# 04_io.net
KiCad netlist of a schematic drawn in Altium Designer
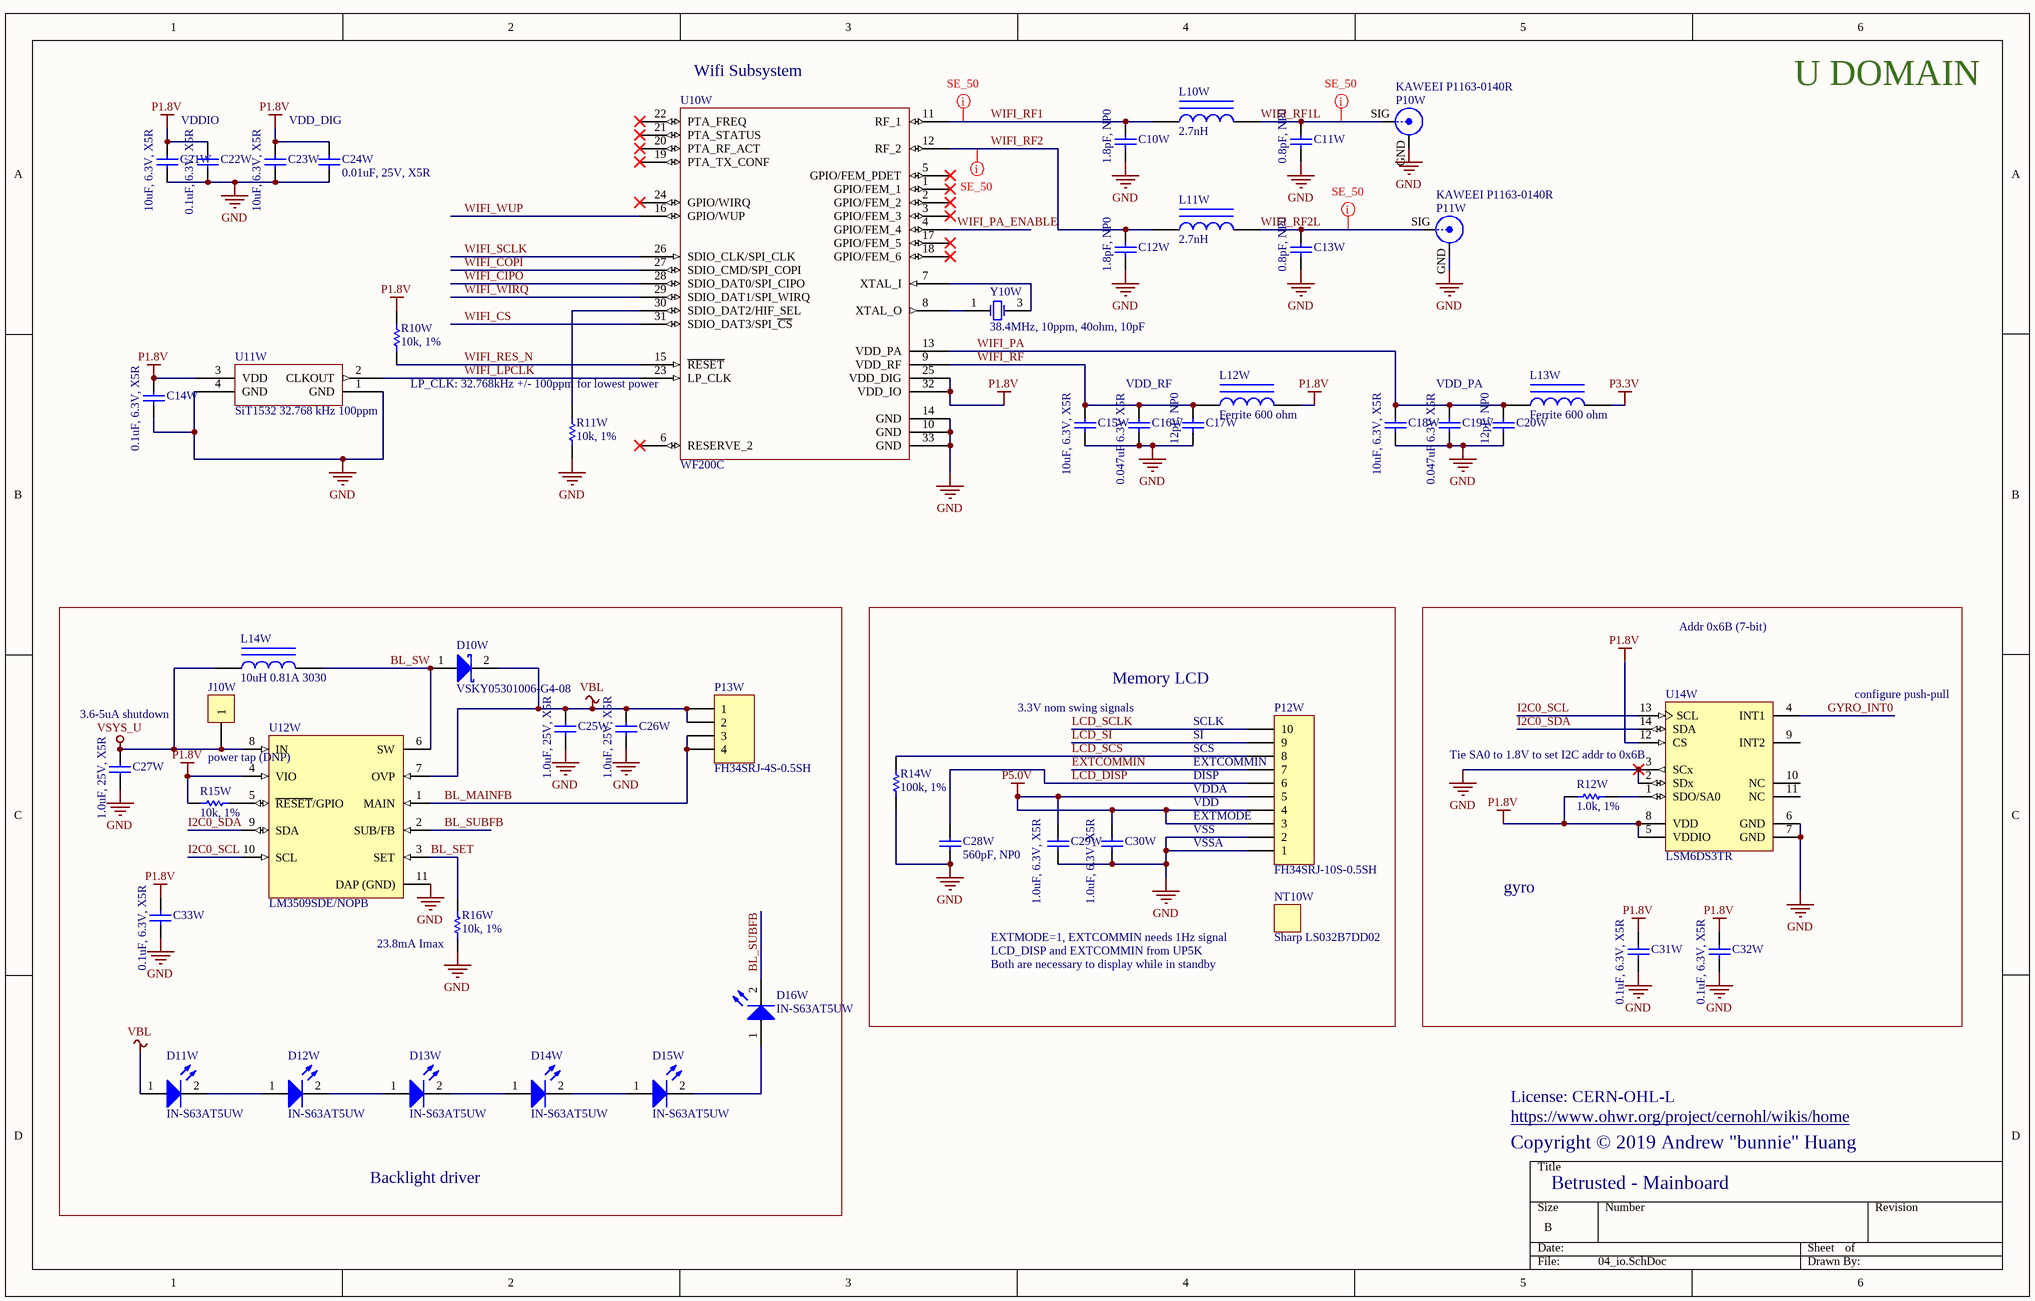
[diagram p0: 04_io.SchDoc]

(export (version "E")
  (design (tool "Eeschema 10.0.6"))
  (components
    (comp (ref "C10W")
      (value "1.8pF, NP0")
      (footprint "B_CAP0201")
      (description "Capacitor (Semiconductor SIM Model)")
      (fields (field (name "MPN") "GRM0335C1H1R8BA01D"))
      (libsource (lib "Miscellaneous Devices") (part "Cap Semi"))
    )
    (comp (ref "C11W")
      (value "0.8pF, NP0")
      (footprint "B_CAP0201")
      (description "Capacitor (Semiconductor SIM Model)")
      (fields (field (name "MPN") "GRM0335C1ER80BA01D"))
      (libsource (lib "Miscellaneous Devices") (part "Cap Semi"))
    )
    (comp (ref "C12W")
      (value "1.8pF, NP0")
      (footprint "B_CAP0201")
      (description "Capacitor (Semiconductor SIM Model)")
      (fields (field (name "MPN") "GRM0335C1H1R8BA01D"))
      (libsource (lib "Miscellaneous Devices") (part "Cap Semi"))
    )
    (comp (ref "C13W")
      (value "0.8pF, NP0")
      (footprint "B_CAP0201")
      (description "Capacitor (Semiconductor SIM Model)")
      (fields (field (name "MPN") "GRM0335C1ER80BA01D"))
      (libsource (lib "Miscellaneous Devices") (part "Cap Semi"))
    )
    (comp (ref "C14W")
      (value "0.1uF, 6.3V, X5R")
      (footprint "B_CAP0201")
      (description "Capacitor (Semiconductor SIM Model)")
      (fields (field (name "MPN") "CL03A104KQ3NNNC"))
      (libsource (lib "Miscellaneous Devices") (part "Cap Semi"))
    )
    (comp (ref "C15W")
      (value "10uF, 6.3V, X5R")
      (footprint "B_CAP0603")
      (description "Capacitor (Semiconductor SIM Model)")
      (fields (field (name "MPN") "CL10A106MQ8NNNC"))
      (libsource (lib "Miscellaneous Devices") (part "Cap Semi"))
    )
    (comp (ref "C16W")
      (value "0.047uF 6.3V X5R")
      (footprint "B_CAP0201")
      (description "Capacitor (Semiconductor SIM Model)")
      (fields (field (name "MPN") "GRM033C81A473KE05D"))
      (libsource (lib "Miscellaneous Devices") (part "Cap Semi"))
    )
    (comp (ref "C17W")
      (value "12pF, NP0")
      (footprint "B_CAP0201")
      (description "Capacitor (Semiconductor SIM Model)")
      (fields (field (name "MPN") "GRM0335C1E120JA01D"))
      (libsource (lib "Miscellaneous Devices") (part "Cap Semi"))
    )
    (comp (ref "C18W")
      (value "10uF, 6.3V, X5R")
      (footprint "B_CAP0603")
      (description "Capacitor (Semiconductor SIM Model)")
      (fields (field (name "MPN") "CL10A106MQ8NNNC"))
      (libsource (lib "Miscellaneous Devices") (part "Cap Semi"))
    )
    (comp (ref "C19W")
      (value "0.047uF 6.3V X5R")
      (footprint "B_CAP0201")
      (description "Capacitor (Semiconductor SIM Model)")
      (fields (field (name "MPN") "GRM033C81A473KE05D"))
      (libsource (lib "Miscellaneous Devices") (part "Cap Semi"))
    )
    (comp (ref "C20W")
      (value "12pF, NP0")
      (footprint "B_CAP0201")
      (description "Capacitor (Semiconductor SIM Model)")
      (fields (field (name "MPN") "GRM0335C1E120JA01D"))
      (libsource (lib "Miscellaneous Devices") (part "Cap Semi"))
    )
    (comp (ref "C21W")
      (value "10uF, 6.3V, X5R")
      (footprint "B_CAP0603")
      (description "Capacitor (Semiconductor SIM Model)")
      (fields (field (name "MPN") "CL10A106MQ8NNNC"))
      (libsource (lib "Miscellaneous Devices") (part "Cap Semi"))
    )
    (comp (ref "C22W")
      (value "0.1uF, 6.3V, X5R")
      (footprint "B_CAP0201")
      (description "Capacitor (Semiconductor SIM Model)")
      (fields (field (name "MPN") "CL03A104KQ3NNNC"))
      (libsource (lib "Miscellaneous Devices") (part "Cap Semi"))
    )
    (comp (ref "C23W")
      (value "10uF, 6.3V, X5R")
      (footprint "B_CAP0603")
      (description "Capacitor (Semiconductor SIM Model)")
      (fields (field (name "MPN") "CL10A106MQ8NNNC"))
      (libsource (lib "Miscellaneous Devices") (part "Cap Semi"))
    )
    (comp (ref "C24W")
      (value "0.01uF, 25V, X5R")
      (footprint "B_RES0201")
      (description "Capacitor (Semiconductor SIM Model)")
      (fields (field (name "MPN") "GRM033R61E103KA12D"))
      (libsource (lib "Miscellaneous Devices") (part "Cap Semi"))
    )
    (comp (ref "C25W")
      (value "1.0uF, 25V, X5R")
      (footprint "B_CAP0603")
      (description "Capacitor (Semiconductor SIM Model)")
      (fields (field (name "MPN") "CL10A105KA8NNNC"))
      (libsource (lib "Miscellaneous Devices") (part "Cap Semi"))
    )
    (comp (ref "C26W")
      (value "1.0uF, 25V, X5R")
      (footprint "B_CAP0603")
      (description "Capacitor (Semiconductor SIM Model)")
      (fields (field (name "MPN") "CL10A105KA8NNNC"))
      (libsource (lib "Miscellaneous Devices") (part "Cap Semi"))
    )
    (comp (ref "C27W")
      (value "1.0uF, 25V, X5R")
      (footprint "B_CAP0603")
      (description "Capacitor (Semiconductor SIM Model)")
      (fields (field (name "MPN") "CL10A105KA8NNNC"))
      (libsource (lib "Miscellaneous Devices") (part "Cap Semi"))
    )
    (comp (ref "C28W")
      (value "560pF, NP0")
      (footprint "B_RES0201")
      (description "Capacitor (Semiconductor SIM Model)")
      (fields (field (name "MPN") "GRM0335C1E561JA01D"))
      (libsource (lib "Miscellaneous Devices") (part "Cap Semi"))
    )
    (comp (ref "C29W")
      (value "1.0uF, 6.3V, X5R")
      (footprint "B_CAP0201")
      (description "Capacitor (Semiconductor SIM Model)")
      (fields (field (name "MPN") "GRM033R60J105MEA2D"))
      (libsource (lib "Miscellaneous Devices") (part "Cap Semi"))
    )
    (comp (ref "C30W")
      (value "1.0uF, 6.3V, X5R")
      (footprint "B_CAP0201")
      (description "Capacitor (Semiconductor SIM Model)")
      (fields (field (name "MPN") "GRM033R60J105MEA2D"))
      (libsource (lib "Miscellaneous Devices") (part "Cap Semi"))
    )
    (comp (ref "C31W")
      (value "0.1uF, 6.3V, X5R")
      (footprint "B_CAP0201")
      (description "Capacitor (Semiconductor SIM Model)")
      (fields (field (name "MPN") "CL03A104KQ3NNNC"))
      (libsource (lib "Miscellaneous Devices") (part "Cap Semi"))
    )
    (comp (ref "C32W")
      (value "0.1uF, 6.3V, X5R")
      (footprint "B_CAP0201")
      (description "Capacitor (Semiconductor SIM Model)")
      (fields (field (name "MPN") "CL03A104KQ3NNNC"))
      (libsource (lib "Miscellaneous Devices") (part "Cap Semi"))
    )
    (comp (ref "C33W")
      (value "0.1uF, 6.3V, X5R")
      (footprint "B_CAP0201")
      (description "Capacitor (Semiconductor SIM Model)")
      (fields (field (name "MPN") "CL03A104KQ3NNNC"))
      (libsource (lib "Miscellaneous Devices") (part "Cap Semi"))
    )
    (comp (ref "D10W")
      (value "VSKY05301006-G4-08")
      (footprint "B_DIO0402")
      (description "Schottky Rectifier")
      (libsource (lib "Miscellaneous Devices") (part "Diode 11DQ03"))
    )
    (comp (ref "D11W")
      (value "IN-S63AT5UW")
      (footprint "B_DIO0603")
      (description "White LED, 0603, 900mcd, 0.4mm")
      (fields (field (name "PUBLISHER") "Altium Limited"))
      (libsource (lib "Miscellaneous Devices") (part "LED2"))
    )
    (comp (ref "D12W")
      (value "IN-S63AT5UW")
      (footprint "B_DIO0603")
      (description "White LED, 0603, 900mcd, 0.4mm")
      (fields (field (name "PUBLISHER") "Altium Limited"))
      (libsource (lib "Miscellaneous Devices") (part "LED2"))
    )
    (comp (ref "D13W")
      (value "IN-S63AT5UW")
      (footprint "B_DIO0603")
      (description "White LED, 0603, 900mcd, 0.4mm")
      (fields (field (name "PUBLISHER") "Altium Limited"))
      (libsource (lib "Miscellaneous Devices") (part "LED2"))
    )
    (comp (ref "D14W")
      (value "IN-S63AT5UW")
      (footprint "B_DIO0603")
      (description "White LED, 0603, 900mcd, 0.4mm")
      (fields (field (name "PUBLISHER") "Altium Limited"))
      (libsource (lib "Miscellaneous Devices") (part "LED2"))
    )
    (comp (ref "D15W")
      (value "IN-S63AT5UW")
      (footprint "B_DIO0603")
      (description "White LED, 0603, 900mcd, 0.4mm")
      (fields (field (name "PUBLISHER") "Altium Limited"))
      (libsource (lib "Miscellaneous Devices") (part "LED2"))
    )
    (comp (ref "D16W")
      (value "IN-S63AT5UW")
      (footprint "B_DIO0603")
      (description "White LED, 0603, 900mcd, 0.4mm")
      (fields (field (name "PUBLISHER") "Altium Limited"))
      (libsource (lib "Miscellaneous Devices") (part "LED2"))
    )
    (comp (ref "J10W")
      (value "power tap (DNP)")
      (footprint "RESTAP-0603")
      (description "Connector")
      (fields (field (name "MPN") "DNP"))
      (libsource (lib "*") (part "CON1"))
    )
    (comp (ref "L10W")
      (value "2.7nH")
      (footprint "B_IND0402")
      (description "Magnetic-Core Inductor")
      (fields (field (name "MPN") "LQW15AN2N7C00"))
      (libsource (lib "Miscellaneous Devices") (part "Inductor Iron"))
    )
    (comp (ref "L11W")
      (value "2.7nH")
      (footprint "B_IND0402")
      (description "Magnetic-Core Inductor")
      (fields (field (name "MPN") "LQW15AN2N7C00"))
      (libsource (lib "Miscellaneous Devices") (part "Inductor Iron"))
    )
    (comp (ref "L12W")
      (value "Ferrite 600 ohm")
      (footprint "B_IND0603")
      (description "Magnetic-Core Inductor")
      (fields (field (name "MPN") "BLM18AG601SN1D"))
      (libsource (lib "Miscellaneous Devices") (part "Inductor Iron"))
    )
    (comp (ref "L13W")
      (value "Ferrite 600 ohm")
      (footprint "B_IND0603")
      (description "Magnetic-Core Inductor")
      (fields (field (name "MPN") "BLM18AG601SN1D"))
      (libsource (lib "Miscellaneous Devices") (part "Inductor Iron"))
    )
    (comp (ref "L14W")
      (value "10uH 0.81A 3030")
      (footprint "B_IND3030_MUR")
      (description "Magnetic-Core Inductor")
      (fields (field (name "MPN") "LQH3NPN100MJRL"))
      (libsource (lib "Miscellaneous Devices") (part "Inductor Iron"))
    )
    (comp (ref "NT10W")
      (value "Sharp LS032B7DD02")
      (description "Placeholder for non-board BOM items")
      (fields (field (name "MPN") "LS032B7DD02"))
      (libsource (lib "commonsch") (part "NOTE"))
    )
    (comp (ref "P10W")
      (value "KAWEEI P1163-0140R")
      (footprint "HRS_U.FL")
      (description "BNC Elbow Connector")
      (fields (field (name "MPN") "P1163-0140R") (field (name "PUBLISHER") "Altium Limited"))
      (libsource (lib "Miscellaneous Connectors") (part "BNC"))
    )
    (comp (ref "P11W")
      (value "KAWEEI P1163-0140R")
      (footprint "HRS_U.FL")
      (description "BNC Elbow Connector")
      (fields (field (name "MPN") "P1163-0140R") (field (name "PUBLISHER") "Altium Limited"))
      (libsource (lib "Miscellaneous Connectors") (part "BNC"))
    )
    (comp (ref "P12W")
      (value "FH34SRJ-10S-0.5SH")
      (footprint "HRS_FH34SRJ-10S-0.5SH(50)")
      (description "Header, 10-Pin")
      (fields (field (name "PUBLISHER") "Altium Limited"))
      (libsource (lib "Miscellaneous Connectors") (part "Header 10"))
    )
    (comp (ref "P13W")
      (value "FH34SRJ-4S-0.5SH")
      (footprint "HRS_FH34SRJ-4S-0.5SH(50)")
      (description "4-pin FPC connector")
      (fields (field (name "MPN") "FH34SRJ-4S-0.5SH(XX)") (field (name "PUBLISHER") "Altium Limited"))
      (libsource (lib "Miscellaneous Connectors") (part "Header 4"))
    )
    (comp (ref "R10W")
      (value "10k, 1%")
      (footprint "B_RES0201")
      (description "Resistor")
      (fields (field (name "MPN") "ANY"))
      (libsource (lib "Miscellaneous Devices") (part "Res1"))
    )
    (comp (ref "R11W")
      (value "10k, 1%")
      (footprint "B_RES0201")
      (description "Resistor")
      (fields (field (name "MPN") "ANY"))
      (libsource (lib "Miscellaneous Devices") (part "Res1"))
    )
    (comp (ref "R12W")
      (value "1.0k, 1%")
      (footprint "B_RES0201")
      (description "Resistor")
      (fields (field (name "MPN") "ANY"))
      (libsource (lib "Miscellaneous Devices") (part "Res1"))
    )
    (comp (ref "R14W")
      (value "100k, 1%")
      (footprint "B_RES0201")
      (description "Resistor")
      (fields (field (name "MPN") "ANY"))
      (libsource (lib "Miscellaneous Devices") (part "Res1"))
    )
    (comp (ref "R15W")
      (value "10k, 1%")
      (footprint "B_RES0201")
      (description "Resistor")
      (fields (field (name "MPN") "ANY"))
      (libsource (lib "Miscellaneous Devices") (part "Res1"))
    )
    (comp (ref "R16W")
      (value "10k, 1%")
      (footprint "B_RES0201")
      (description "Resistor")
      (fields (field (name "MPN") "ANY"))
      (libsource (lib "Miscellaneous Devices") (part "Res1"))
    )
    (comp (ref "U10W")
      (value "WF200C")
      (footprint "QFN40P400X400X90_HS-33N")
      (description "Wifi Network Coprocessor")
      (libsource (lib "commonsch-new") (part "WF200C(R)"))
    )
    (comp (ref "U11W")
      (value "SiT1532 32.768 kHz 100ppm")
      (footprint "SiTIME_CSP")
      (description "10ppm ultra low power 32.768 kHz replacement")
      (fields (field (name "MPN") "SIT1532AI-J4-DCC-32.768E"))
      (libsource (lib "altium-import") (part "root_2_SiT1532_"))
    )
    (comp (ref "U12W")
      (value "LM3509SDE/NOPB")
      (footprint "DSC0010A_V")
      (libsource (lib "commonsch-new") (part "LM3509SDE/NOPB"))
    )
    (comp (ref "U14W")
      (value "LSM6DS3TR")
      (footprint "LGA-14_2500X3000X860_N")
      (libsource (lib "commonsch-new") (part "LSM6DS3TR"))
    )
    (comp (ref "Y10W")
      (value "38.4MHz, 10ppm, 40ohm, 10pF")
      (footprint "XOSC_3.2_2.5")
      (description "Crystal Oscillator")
      (fields (field (name "MPN") "ECS-384-10-33B-CKY-TR") (field (name "PUBLISHER") "Altium Limited"))
      (libsource (lib "Miscellaneous Devices") (part "XTAL"))
    )
  )
  (nets
    (net (code "1") (name "/BL_MAINFB") (class "Default")
      (node (ref "P13W") (pin "3") (pinfunction "3_3") (pintype "passive"))
      (node (ref "P13W") (pin "4") (pinfunction "4_4") (pintype "passive"))
      (node (ref "U12W") (pin "1") (pinfunction "MAIN_1") (pintype "input"))
    )
    (net (code "2") (name "/BL_SET") (class "Default")
      (node (ref "R16W") (pin "1") (pinfunction "1_1") (pintype "passive"))
      (node (ref "U12W") (pin "3") (pinfunction "SET_3") (pintype "input"))
    )
    (net (code "3") (name "/BL_SUBFB") (class "Default")
      (node (ref "D16W") (pin "2") (pinfunction "K_2") (pintype "passive"))
      (node (ref "U12W") (pin "2") (pinfunction "SUB/FB_2") (pintype "input"))
    )
    (net (code "4") (name "/BL_SW") (class "Default")
      (node (ref "D10W") (pin "1") (pinfunction "A_1") (pintype "passive"))
      (node (ref "L14W") (pin "2") (pinfunction "2_2") (pintype "passive"))
      (node (ref "U12W") (pin "6") (pinfunction "SW_6") (pintype "power_in"))
    )
    (net (code "5") (name "/EXTCOMMIN") (class "Default")
      (node (ref "P12W") (pin "7") (pinfunction "7_7") (pintype "passive"))
    )
    (net (code "6") (name "/GYRO_INT0") (class "Default")
      (node (ref "U14W") (pin "4") (pinfunction "INT1_4") (pintype "open_collector"))
    )
    (net (code "7") (name "/I2C0_SCL") (class "Default")
      (node (ref "U12W") (pin "10") (pinfunction "SCL_10") (pintype "input"))
      (node (ref "U14W") (pin "13") (pinfunction "SCL_13") (pintype "input"))
    )
    (net (code "8") (name "/I2C0_SDA") (class "Default")
      (node (ref "U12W") (pin "9") (pinfunction "SDA_9") (pintype "bidirectional"))
      (node (ref "U14W") (pin "14") (pinfunction "SDA_14") (pintype "bidirectional"))
    )
    (net (code "9") (name "/LCD_DISP") (class "Default")
      (node (ref "C28W") (pin "1") (pinfunction "1_1") (pintype "passive"))
      (node (ref "P12W") (pin "6") (pinfunction "6_6") (pintype "passive"))
    )
    (net (code "10") (name "/LCD_SCLK") (class "Default")
      (node (ref "P12W") (pin "10") (pinfunction "10_10") (pintype "passive"))
    )
    (net (code "11") (name "/LCD_SCS") (class "Default")
      (node (ref "P12W") (pin "8") (pinfunction "8_8") (pintype "passive"))
      (node (ref "R14W") (pin "2") (pinfunction "2_2") (pintype "passive"))
    )
    (net (code "12") (name "/LCD_SI") (class "Default")
      (node (ref "P12W") (pin "9") (pinfunction "9_9") (pintype "passive"))
    )
    (net (code "13") (name "/WIFI_CIPO") (class "Default")
      (node (ref "U10W") (pin "28") (pinfunction "SDIO_DAT0/SPI_CIPO_28") (pintype "bidirectional"))
    )
    (net (code "14") (name "/WIFI_COPI") (class "Default")
      (node (ref "U10W") (pin "27") (pinfunction "SDIO_CMD/SPI_COPI_27") (pintype "bidirectional"))
    )
    (net (code "15") (name "/WIFI_CS") (class "Default")
      (node (ref "U10W") (pin "31") (pinfunction "SDIO_DAT3/SPI_~{CS}_31") (pintype "bidirectional"))
    )
    (net (code "16") (name "/WIFI_LPCLK") (class "Default")
      (node (ref "U10W") (pin "23") (pinfunction "LP_CLK_23") (pintype "input"))
      (node (ref "U11W") (pin "2") (pinfunction "CLKOUT_2") (pintype "output"))
    )
    (net (code "17") (name "/WIFI_PA") (class "Default")
      (node (ref "C18W") (pin "1") (pinfunction "1_1") (pintype "passive"))
      (node (ref "C19W") (pin "1") (pinfunction "1_1") (pintype "passive"))
      (node (ref "C20W") (pin "1") (pinfunction "1_1") (pintype "passive"))
      (node (ref "L13W") (pin "1") (pinfunction "1_1") (pintype "passive"))
      (node (ref "U10W") (pin "13") (pinfunction "VDD_PA_13") (pintype "power_in"))
    )
    (net (code "18") (name "/WIFI_PA_ENABLE") (class "Default")
      (node (ref "U10W") (pin "4") (pinfunction "GPIO/FEM_4_4") (pintype "bidirectional"))
    )
    (net (code "19") (name "/WIFI_RES_N") (class "Default")
      (node (ref "R10W") (pin "2") (pinfunction "2_2") (pintype "passive"))
      (node (ref "U10W") (pin "15") (pinfunction "~{RESET}_15") (pintype "input"))
    )
    (net (code "20") (name "/WIFI_RF") (class "Default")
      (node (ref "C15W") (pin "1") (pinfunction "1_1") (pintype "passive"))
      (node (ref "C16W") (pin "1") (pinfunction "1_1") (pintype "passive"))
      (node (ref "C17W") (pin "1") (pinfunction "1_1") (pintype "passive"))
      (node (ref "L12W") (pin "1") (pinfunction "1_1") (pintype "passive"))
      (node (ref "U10W") (pin "9") (pinfunction "VDD_RF_9") (pintype "power_in"))
    )
    (net (code "21") (name "/WIFI_RF1") (class "Default")
      (node (ref "C10W") (pin "1") (pinfunction "1_1") (pintype "passive"))
      (node (ref "L10W") (pin "1") (pinfunction "1_1") (pintype "passive"))
      (node (ref "U10W") (pin "11") (pinfunction "RF_1_11") (pintype "bidirectional"))
    )
    (net (code "22") (name "/WIFI_RF1L") (class "Default")
      (node (ref "C11W") (pin "1") (pinfunction "1_1") (pintype "passive"))
      (node (ref "L10W") (pin "2") (pinfunction "2_2") (pintype "passive"))
      (node (ref "P10W") (pin "SIG") (pinfunction "X_SIG") (pintype "passive"))
    )
    (net (code "23") (name "/WIFI_RF2") (class "Default")
      (node (ref "C12W") (pin "1") (pinfunction "1_1") (pintype "passive"))
      (node (ref "L11W") (pin "1") (pinfunction "1_1") (pintype "passive"))
      (node (ref "U10W") (pin "12") (pinfunction "RF_2_12") (pintype "bidirectional"))
    )
    (net (code "24") (name "/WIFI_RF2L") (class "Default")
      (node (ref "C13W") (pin "1") (pinfunction "1_1") (pintype "passive"))
      (node (ref "L11W") (pin "2") (pinfunction "2_2") (pintype "passive"))
      (node (ref "P11W") (pin "SIG") (pinfunction "X_SIG") (pintype "passive"))
    )
    (net (code "25") (name "/WIFI_SCLK") (class "Default")
      (node (ref "U10W") (pin "26") (pinfunction "SDIO_CLK/SPI_CLK_26") (pintype "input"))
    )
    (net (code "26") (name "/WIFI_WIRQ") (class "Default")
      (node (ref "U10W") (pin "29") (pinfunction "SDIO_DAT1/SPI_WIRQ_29") (pintype "bidirectional"))
    )
    (net (code "27") (name "/WIFI_WUP") (class "Default")
      (node (ref "U10W") (pin "16") (pinfunction "GPIO/WUP_16") (pintype "bidirectional"))
    )
    (net (code "28") (name "GND") (class "Default")
      (node (ref "C10W") (pin "2") (pinfunction "2_2") (pintype "passive"))
      (node (ref "C11W") (pin "2") (pinfunction "2_2") (pintype "passive"))
      (node (ref "C12W") (pin "2") (pinfunction "2_2") (pintype "passive"))
      (node (ref "C13W") (pin "2") (pinfunction "2_2") (pintype "passive"))
      (node (ref "C14W") (pin "2") (pinfunction "2_2") (pintype "passive"))
      (node (ref "C15W") (pin "2") (pinfunction "2_2") (pintype "passive"))
      (node (ref "C16W") (pin "2") (pinfunction "2_2") (pintype "passive"))
      (node (ref "C17W") (pin "2") (pinfunction "2_2") (pintype "passive"))
      (node (ref "C18W") (pin "2") (pinfunction "2_2") (pintype "passive"))
      (node (ref "C19W") (pin "2") (pinfunction "2_2") (pintype "passive"))
      (node (ref "C20W") (pin "2") (pinfunction "2_2") (pintype "passive"))
      (node (ref "C21W") (pin "2") (pinfunction "2_2") (pintype "passive"))
      (node (ref "C22W") (pin "2") (pinfunction "2_2") (pintype "passive"))
      (node (ref "C23W") (pin "2") (pinfunction "2_2") (pintype "passive"))
      (node (ref "C24W") (pin "2") (pinfunction "2_2") (pintype "passive"))
      (node (ref "C25W") (pin "2") (pinfunction "2_2") (pintype "passive"))
      (node (ref "C26W") (pin "2") (pinfunction "2_2") (pintype "passive"))
      (node (ref "C27W") (pin "2") (pinfunction "2_2") (pintype "passive"))
      (node (ref "C28W") (pin "2") (pinfunction "2_2") (pintype "passive"))
      (node (ref "C29W") (pin "1") (pinfunction "1_1") (pintype "passive"))
      (node (ref "C30W") (pin "1") (pinfunction "1_1") (pintype "passive"))
      (node (ref "C31W") (pin "2") (pinfunction "2_2") (pintype "passive"))
      (node (ref "C32W") (pin "2") (pinfunction "2_2") (pintype "passive"))
      (node (ref "C33W") (pin "2") (pinfunction "2_2") (pintype "passive"))
      (node (ref "P10W") (pin "GND") (pinfunction "Y_GND") (pintype "passive"))
      (node (ref "P11W") (pin "GND") (pinfunction "Y_GND") (pintype "passive"))
      (node (ref "P12W") (pin "1") (pinfunction "1_1") (pintype "passive"))
      (node (ref "P12W") (pin "2") (pinfunction "2_2") (pintype "passive"))
      (node (ref "R11W") (pin "2") (pinfunction "2_2") (pintype "passive"))
      (node (ref "R14W") (pin "1") (pinfunction "1_1") (pintype "passive"))
      (node (ref "R16W") (pin "2") (pinfunction "2_2") (pintype "passive"))
      (node (ref "U10W") (pin "10") (pinfunction "GND_10") (pintype "power_in"))
      (node (ref "U10W") (pin "14") (pinfunction "GND_14") (pintype "power_in"))
      (node (ref "U10W") (pin "33") (pinfunction "GND_33") (pintype "power_in"))
      (node (ref "U11W") (pin "1") (pinfunction "GND_1") (pintype "power_in"))
      (node (ref "U11W") (pin "4") (pinfunction "GND_4") (pintype "power_in"))
      (node (ref "U12W") (pin "11") (pinfunction "DAP_(GND)_11") (pintype "power_in"))
      (node (ref "U14W") (pin "2") (pinfunction "SDx_2") (pintype "bidirectional"))
      (node (ref "U14W") (pin "3") (pinfunction "SCx_3") (pintype "output"))
      (node (ref "U14W") (pin "6") (pinfunction "GND_6") (pintype "power_in"))
      (node (ref "U14W") (pin "7") (pinfunction "GND_7") (pintype "power_in"))
    )
    (net (code "29") (name "Net-(D11W-K)") (class "Default")
      (node (ref "D11W") (pin "2") (pinfunction "K_2") (pintype "passive"))
      (node (ref "D12W") (pin "1") (pinfunction "A_1") (pintype "passive"))
    )
    (net (code "30") (name "Net-(D12W-K)") (class "Default")
      (node (ref "D12W") (pin "2") (pinfunction "K_2") (pintype "passive"))
      (node (ref "D13W") (pin "1") (pinfunction "A_1") (pintype "passive"))
    )
    (net (code "31") (name "Net-(D13W-K)") (class "Default")
      (node (ref "D13W") (pin "2") (pinfunction "K_2") (pintype "passive"))
      (node (ref "D14W") (pin "1") (pinfunction "A_1") (pintype "passive"))
    )
    (net (code "32") (name "Net-(D14W-K)") (class "Default")
      (node (ref "D14W") (pin "2") (pinfunction "K_2") (pintype "passive"))
      (node (ref "D15W") (pin "1") (pinfunction "A_1") (pintype "passive"))
    )
    (net (code "33") (name "Net-(D15W-K)") (class "Default")
      (node (ref "D15W") (pin "2") (pinfunction "K_2") (pintype "passive"))
      (node (ref "D16W") (pin "1") (pinfunction "A_1") (pintype "passive"))
    )
    (net (code "34") (name "Net-(U10W-SDIO_DAT2{slash}HIF_SEL)") (class "Default")
      (node (ref "R11W") (pin "1") (pinfunction "1_1") (pintype "passive"))
      (node (ref "U10W") (pin "30") (pinfunction "SDIO_DAT2/HIF_SEL_30") (pintype "bidirectional"))
    )
    (net (code "35") (name "Net-(U10W-XTAL_I)") (class "Default")
      (node (ref "U10W") (pin "7") (pinfunction "XTAL_I_7") (pintype "input"))
      (node (ref "Y10W") (pin "3") (pinfunction "OSC2_3") (pintype "passive"))
    )
    (net (code "36") (name "Net-(U10W-XTAL_O)") (class "Default")
      (node (ref "U10W") (pin "8") (pinfunction "XTAL_O_8") (pintype "output"))
      (node (ref "Y10W") (pin "1") (pinfunction "OSC1_1") (pintype "passive"))
    )
    (net (code "37") (name "Net-(U12W-~{RESET}{slash}GPIO)") (class "Default")
      (node (ref "R15W") (pin "2") (pinfunction "2_2") (pintype "passive"))
      (node (ref "U12W") (pin "5") (pinfunction "~{RESET}/GPIO_5") (pintype "bidirectional"))
    )
    (net (code "38") (name "Net-(U14W-SDO{slash}SA0)") (class "Default")
      (node (ref "R12W") (pin "1") (pinfunction "1_1") (pintype "passive"))
      (node (ref "U14W") (pin "1") (pinfunction "SDO/SA0_1") (pintype "bidirectional"))
    )
    (net (code "39") (name "P1.8V") (class "Default")
      (node (ref "C14W") (pin "1") (pinfunction "1_1") (pintype "passive"))
      (node (ref "C21W") (pin "1") (pinfunction "1_1") (pintype "passive"))
      (node (ref "C22W") (pin "1") (pinfunction "1_1") (pintype "passive"))
      (node (ref "C23W") (pin "1") (pinfunction "1_1") (pintype "passive"))
      (node (ref "C24W") (pin "1") (pinfunction "1_1") (pintype "passive"))
      (node (ref "C31W") (pin "1") (pinfunction "1_1") (pintype "passive"))
      (node (ref "C32W") (pin "1") (pinfunction "1_1") (pintype "passive"))
      (node (ref "C33W") (pin "1") (pinfunction "1_1") (pintype "passive"))
      (node (ref "L12W") (pin "2") (pinfunction "2_2") (pintype "passive"))
      (node (ref "R10W") (pin "1") (pinfunction "1_1") (pintype "passive"))
      (node (ref "R12W") (pin "2") (pinfunction "2_2") (pintype "passive"))
      (node (ref "R15W") (pin "1") (pinfunction "1_1") (pintype "passive"))
      (node (ref "U10W") (pin "25") (pinfunction "VDD_DIG_25") (pintype "power_in"))
      (node (ref "U10W") (pin "32") (pinfunction "VDD_IO_32") (pintype "power_in"))
      (node (ref "U11W") (pin "3") (pinfunction "VDD_3") (pintype "power_in"))
      (node (ref "U12W") (pin "4") (pinfunction "VIO_4") (pintype "input"))
      (node (ref "U14W") (pin "12") (pinfunction "CS_12") (pintype "input"))
      (node (ref "U14W") (pin "5") (pinfunction "VDDIO_5") (pintype "power_in"))
      (node (ref "U14W") (pin "8") (pinfunction "VDD_8") (pintype "power_in"))
    )
    (net (code "40") (name "P3.3V") (class "Default")
      (node (ref "L13W") (pin "2") (pinfunction "2_2") (pintype "passive"))
    )
    (net (code "41") (name "P5.0V") (class "Default")
      (node (ref "C29W") (pin "2") (pinfunction "2_2") (pintype "passive"))
      (node (ref "C30W") (pin "2") (pinfunction "2_2") (pintype "passive"))
      (node (ref "P12W") (pin "3") (pinfunction "3_3") (pintype "passive"))
      (node (ref "P12W") (pin "4") (pinfunction "4_4") (pintype "passive"))
      (node (ref "P12W") (pin "5") (pinfunction "5_5") (pintype "passive"))
    )
    (net (code "42") (name "VBL") (class "Default")
      (node (ref "C25W") (pin "1") (pinfunction "1_1") (pintype "passive"))
      (node (ref "C26W") (pin "1") (pinfunction "1_1") (pintype "passive"))
      (node (ref "D10W") (pin "2") (pinfunction "K_2") (pintype "passive"))
      (node (ref "D11W") (pin "1") (pinfunction "A_1") (pintype "passive"))
      (node (ref "P13W") (pin "1") (pinfunction "1_1") (pintype "passive"))
      (node (ref "P13W") (pin "2") (pinfunction "2_2") (pintype "passive"))
      (node (ref "U12W") (pin "7") (pinfunction "OVP_7") (pintype "input"))
    )
    (net (code "43") (name "VSYS_U") (class "Default")
      (node (ref "C27W") (pin "1") (pinfunction "1_1") (pintype "passive"))
      (node (ref "J10W") (pin "1") (pinfunction "1_1") (pintype "passive"))
      (node (ref "L14W") (pin "1") (pinfunction "1_1") (pintype "passive"))
      (node (ref "U12W") (pin "8") (pinfunction "IN_8") (pintype "input"))
    )
    (net (code "44") (name "unconnected-(U10W-GPIO{slash}FEM_1-Pad1)") (class "Default")
      (node (ref "U10W") (pin "1") (pinfunction "GPIO/FEM_1_1") (pintype "bidirectional+no_connect"))
    )
    (net (code "45") (name "unconnected-(U10W-GPIO{slash}FEM_2-Pad2)") (class "Default")
      (node (ref "U10W") (pin "2") (pinfunction "GPIO/FEM_2_2") (pintype "bidirectional+no_connect"))
    )
    (net (code "46") (name "unconnected-(U10W-GPIO{slash}FEM_3-Pad3)") (class "Default")
      (node (ref "U10W") (pin "3") (pinfunction "GPIO/FEM_3_3") (pintype "bidirectional+no_connect"))
    )
    (net (code "47") (name "unconnected-(U10W-GPIO{slash}FEM_5-Pad17)") (class "Default")
      (node (ref "U10W") (pin "17") (pinfunction "GPIO/FEM_5_17") (pintype "bidirectional+no_connect"))
    )
    (net (code "48") (name "unconnected-(U10W-GPIO{slash}FEM_6-Pad18)") (class "Default")
      (node (ref "U10W") (pin "18") (pinfunction "GPIO/FEM_6_18") (pintype "bidirectional+no_connect"))
    )
    (net (code "49") (name "unconnected-(U10W-GPIO{slash}FEM_PDET-Pad5)") (class "Default")
      (node (ref "U10W") (pin "5") (pinfunction "GPIO/FEM_PDET_5") (pintype "bidirectional+no_connect"))
    )
    (net (code "50") (name "unconnected-(U10W-GPIO{slash}WIRQ-Pad24)") (class "Default")
      (node (ref "U10W") (pin "24") (pinfunction "GPIO/WIRQ_24") (pintype "bidirectional+no_connect"))
    )
    (net (code "51") (name "unconnected-(U10W-PTA_FREQ-Pad22)") (class "Default")
      (node (ref "U10W") (pin "22") (pinfunction "PTA_FREQ_22") (pintype "bidirectional+no_connect"))
    )
    (net (code "52") (name "unconnected-(U10W-PTA_RF_ACT-Pad20)") (class "Default")
      (node (ref "U10W") (pin "20") (pinfunction "PTA_RF_ACT_20") (pintype "bidirectional+no_connect"))
    )
    (net (code "53") (name "unconnected-(U10W-PTA_STATUS-Pad21)") (class "Default")
      (node (ref "U10W") (pin "21") (pinfunction "PTA_STATUS_21") (pintype "bidirectional+no_connect"))
    )
    (net (code "54") (name "unconnected-(U10W-PTA_TX_CONF-Pad19)") (class "Default")
      (node (ref "U10W") (pin "19") (pinfunction "PTA_TX_CONF_19") (pintype "bidirectional+no_connect"))
    )
    (net (code "55") (name "unconnected-(U10W-RESERVE_2-Pad6)") (class "Default")
      (node (ref "U10W") (pin "6") (pinfunction "RESERVE_2_6") (pintype "bidirectional+no_connect"))
    )
    (net (code "56") (name "unconnected-(U14W-INT2-Pad9)") (class "Default")
      (node (ref "U14W") (pin "9") (pinfunction "INT2_9") (pintype "open_collector"))
    )
    (net (code "57") (name "unconnected-(U14W-NC-Pad10)") (class "Default")
      (node (ref "U14W") (pin "10") (pinfunction "NC_10") (pintype "passive"))
    )
    (net (code "58") (name "unconnected-(U14W-NC-Pad11)") (class "Default")
      (node (ref "U14W") (pin "11") (pinfunction "NC_11") (pintype "passive"))
    )
  )
)
